# 485.net
KiCad netlist of a schematic drawn in Altium Designer
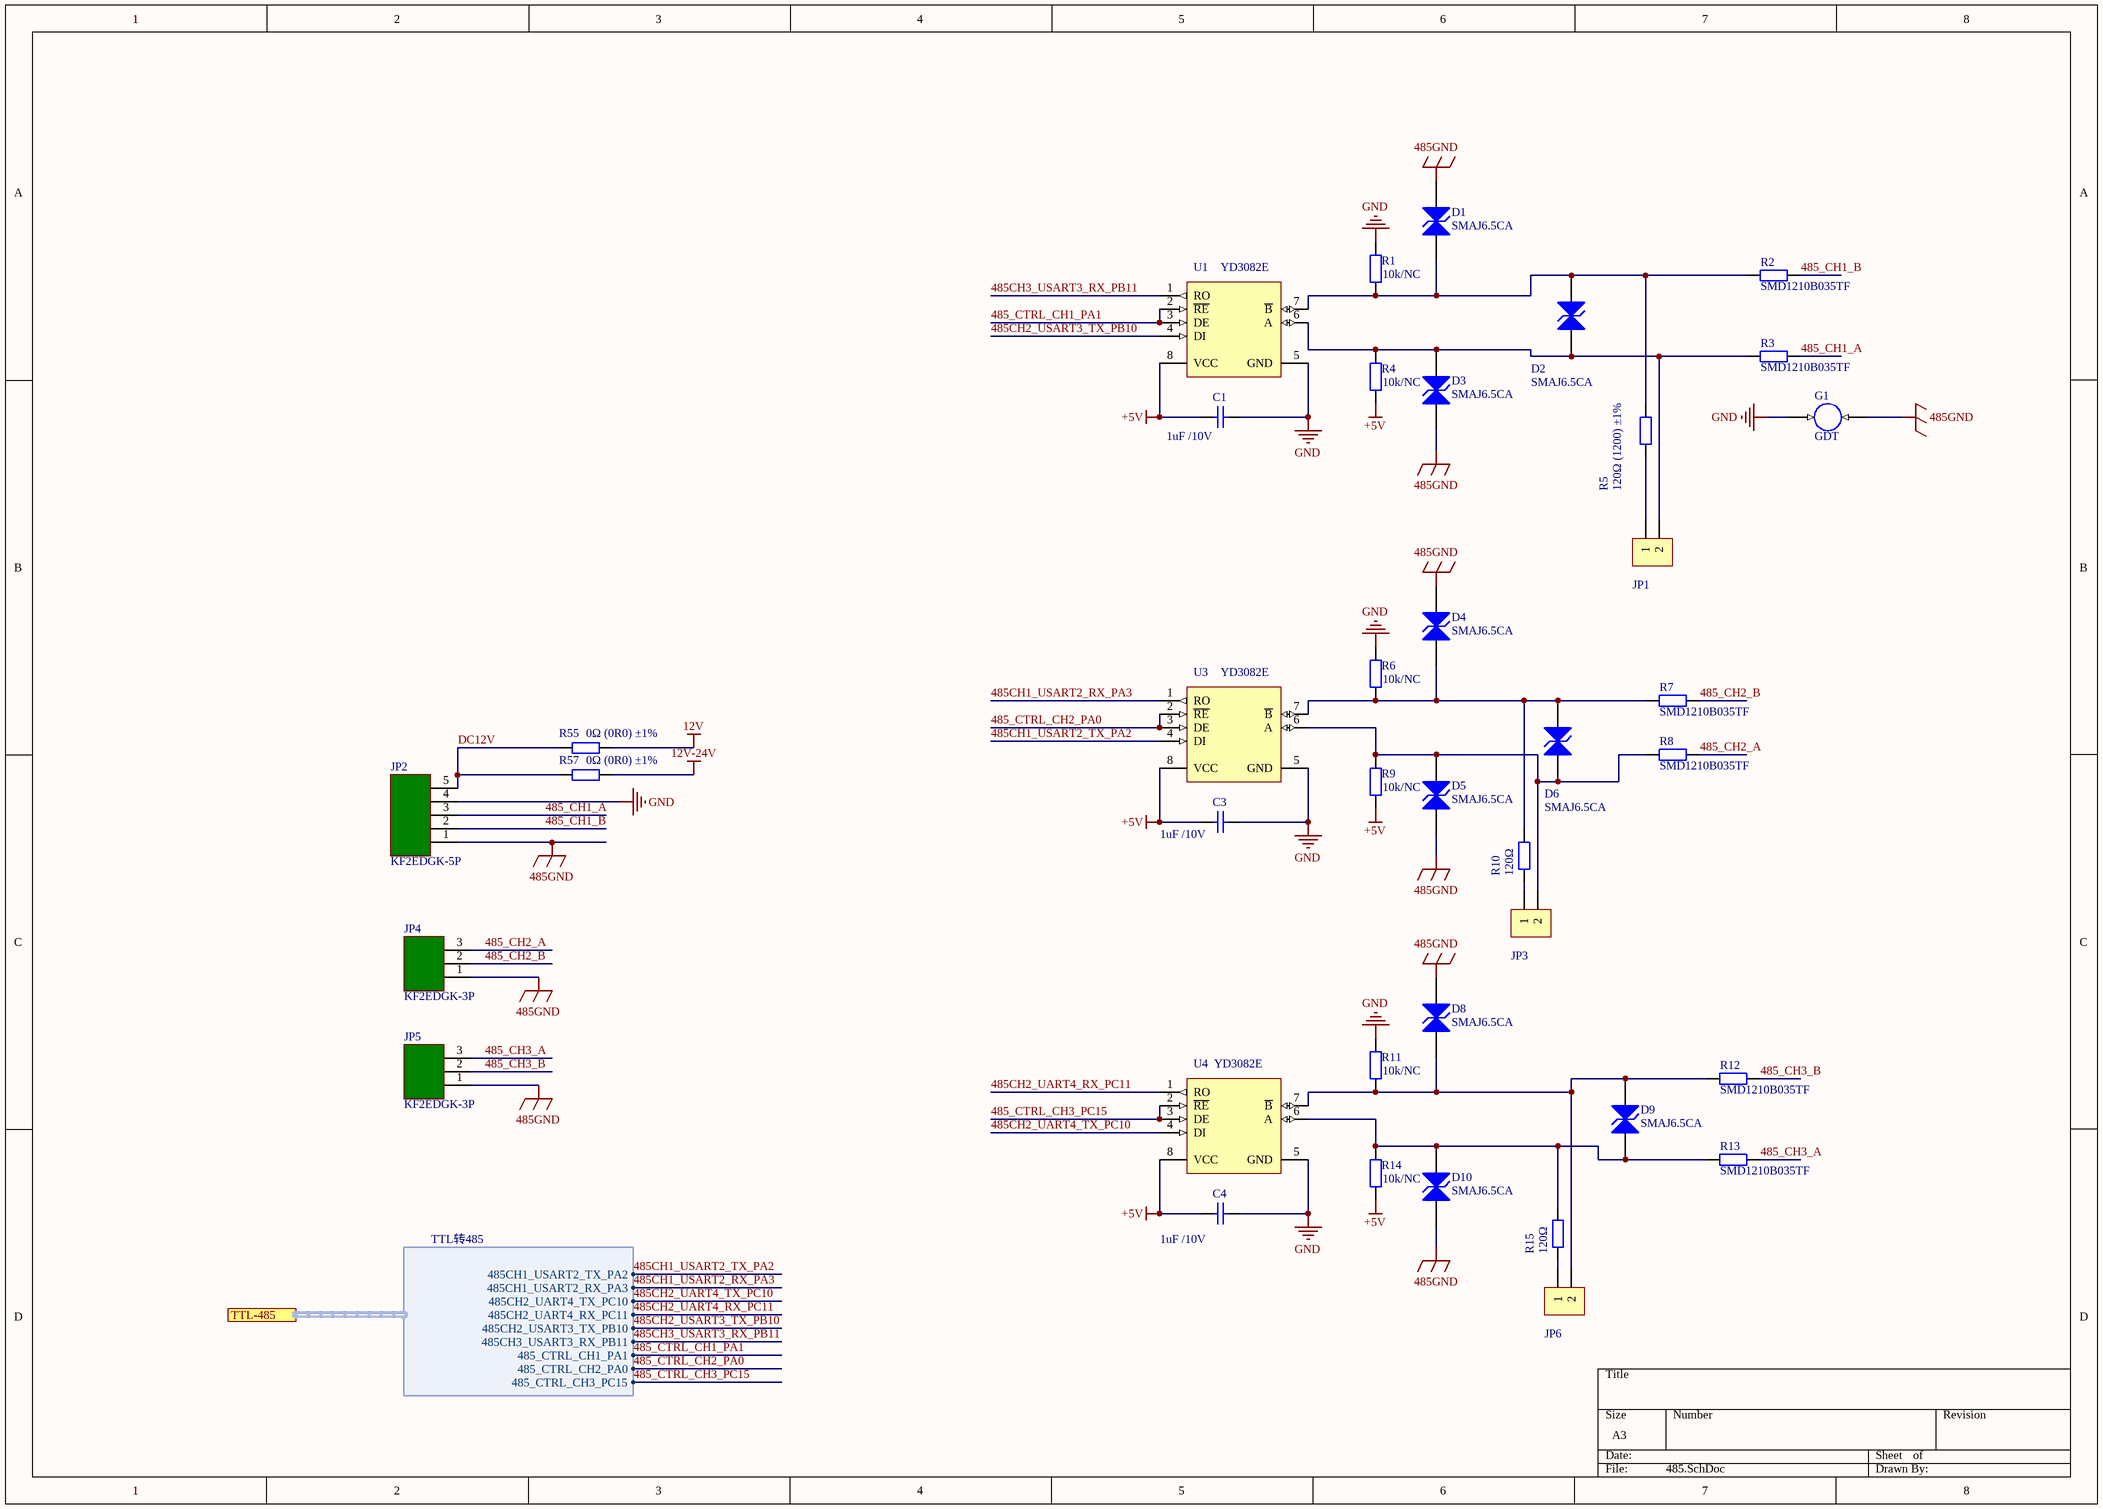
[diagram p0: 485.SchDoc]

(export (version "E")
  (design (tool "Eeschema 10.0.6"))
  (components
    (comp (ref "C1")
      (value "1uF /10V")
      (footprint "0603_C")
      (description "贴片电容")
      (libsource (lib "Miscellaneous Devices LC") (part "0603 100nF (104) 10% 50V"))
    )
    (comp (ref "C3")
      (value "1uF /10V")
      (footprint "0603_C")
      (description "贴片电容")
      (libsource (lib "Miscellaneous Devices LC") (part "0603 100nF (104) 10% 50V"))
    )
    (comp (ref "C4")
      (value "1uF /10V")
      (footprint "0603_C")
      (description "贴片电容")
      (libsource (lib "Miscellaneous Devices LC") (part "0603 100nF (104) 10% 50V"))
    )
    (comp (ref "D1")
      (value "SMAJ6.5CA")
      (footprint "SMA(DO-214AC)_S1")
      (description "TVS")
      (libsource (lib "Miscellaneous Devices LC") (part "SMB/DO-214AA P6SMB6.8CA"))
    )
    (comp (ref "D2")
      (value "SMAJ6.5CA")
      (footprint "SMA(DO-214AC)_S1")
      (description "TVS")
      (libsource (lib "Miscellaneous Devices LC") (part "SMB/DO-214AA P6SMB6.8CA"))
    )
    (comp (ref "D3")
      (value "SMAJ6.5CA")
      (footprint "SMA(DO-214AC)_S1")
      (description "TVS")
      (libsource (lib "Miscellaneous Devices LC") (part "SMB/DO-214AA P6SMB6.8CA"))
    )
    (comp (ref "D4")
      (value "SMAJ6.5CA")
      (footprint "SMA(DO-214AC)_S1")
      (description "TVS")
      (libsource (lib "Miscellaneous Devices LC") (part "SMB/DO-214AA P6SMB6.8CA"))
    )
    (comp (ref "D5")
      (value "SMAJ6.5CA")
      (footprint "SMA(DO-214AC)_S1")
      (description "TVS")
      (libsource (lib "Miscellaneous Devices LC") (part "SMB/DO-214AA P6SMB6.8CA"))
    )
    (comp (ref "D6")
      (value "SMAJ6.5CA")
      (footprint "SMA(DO-214AC)_S1")
      (description "TVS")
      (libsource (lib "Miscellaneous Devices LC") (part "SMB/DO-214AA P6SMB6.8CA"))
    )
    (comp (ref "D8")
      (value "SMAJ6.5CA")
      (footprint "SMA(DO-214AC)_S1")
      (description "TVS")
      (libsource (lib "Miscellaneous Devices LC") (part "SMB/DO-214AA P6SMB6.8CA"))
    )
    (comp (ref "D9")
      (value "SMAJ6.5CA")
      (footprint "SMA(DO-214AC)_S1")
      (description "TVS")
      (libsource (lib "Miscellaneous Devices LC") (part "SMB/DO-214AA P6SMB6.8CA"))
    )
    (comp (ref "D10")
      (value "SMAJ6.5CA")
      (footprint "SMA(DO-214AC)_S1")
      (description "TVS")
      (libsource (lib "Miscellaneous Devices LC") (part "SMB/DO-214AA P6SMB6.8CA"))
    )
    (comp (ref "G1")
      (value "GDT")
      (footprint "GDT")
      (description "放电管")
      (libsource (lib "this") (part "GDT"))
    )
    (comp (ref "JP1")
      (value "HDR-1X2")
      (footprint "HDR-1X2")
      (description "2P接插件")
      (fields (field (name "版权归属") "源创客"))
      (libsource (lib "源创客") (part "Header 2"))
    )
    (comp (ref "JP2")
      (value "KF2EDGK-5P")
      (footprint "KF2EDGK5.08W-5P")
      (libsource (lib "KF2EDGK") (part "KF2EDGK-5P"))
    )
    (comp (ref "JP3")
      (value "HDR-1X2")
      (footprint "HDR-1X2")
      (description "2P接插件")
      (fields (field (name "版权归属") "源创客"))
      (libsource (lib "源创客") (part "Header 2"))
    )
    (comp (ref "JP4")
      (value "KF2EDGK-3P")
      (footprint "KF2EDGK5.08W-3P")
      (libsource (lib "KF2EDGK") (part "KF2EDGK-3P"))
    )
    (comp (ref "JP5")
      (value "KF2EDGK-3P")
      (footprint "KF2EDGK5.08W-3P")
      (libsource (lib "KF2EDGK") (part "KF2EDGK-3P"))
    )
    (comp (ref "JP6")
      (value "HDR-1X2")
      (footprint "HDR-1X2")
      (description "2P接插件")
      (fields (field (name "版权归属") "源创客"))
      (libsource (lib "源创客") (part "Header 2"))
    )
    (comp (ref "R1")
      (value "10k/NC")
      (footprint "0603_R")
      (description "贴片电阻")
      (libsource (lib "Miscellaneous Devices LC") (part "0603 3.3KΩ (3301) 1%"))
    )
    (comp (ref "R2")
      (value "SMD1210B035TF")
      (footprint "1206_R")
      (description "贴片电阻")
      (libsource (lib "Miscellaneous Devices LC") (part "1206 0Ω (0R0) 1%"))
    )
    (comp (ref "R3")
      (value "SMD1210B035TF")
      (footprint "1206_R")
      (description "贴片电阻")
      (libsource (lib "Miscellaneous Devices LC") (part "1206 0Ω (0R0) 1%"))
    )
    (comp (ref "R4")
      (value "10k/NC")
      (footprint "0603_R")
      (description "贴片电阻")
      (libsource (lib "Miscellaneous Devices LC") (part "0603 3.3KΩ (3301) 1%"))
    )
    (comp (ref "R5")
      (value "120Ω (1200) ±1%")
      (footprint "0603_R")
      (description "贴片电阻")
      (libsource (lib "Miscellaneous Devices LC") (part "0603 120Ω (1200) 1%"))
    )
    (comp (ref "R6")
      (value "10k/NC")
      (footprint "0603_R")
      (description "贴片电阻")
      (libsource (lib "Miscellaneous Devices LC") (part "0603 3.3KΩ (3301) 1%"))
    )
    (comp (ref "R7")
      (value "SMD1210B035TF")
      (footprint "1206_R")
      (description "贴片电阻")
      (libsource (lib "Miscellaneous Devices LC") (part "1206 0Ω (0R0) 1%"))
    )
    (comp (ref "R8")
      (value "SMD1210B035TF")
      (footprint "1206_R")
      (description "贴片电阻")
      (libsource (lib "Miscellaneous Devices LC") (part "1206 0Ω (0R0) 1%"))
    )
    (comp (ref "R9")
      (value "10k/NC")
      (footprint "0603_R")
      (description "贴片电阻")
      (libsource (lib "Miscellaneous Devices LC") (part "0603 3.3KΩ (3301) 1%"))
    )
    (comp (ref "R10")
      (value "120Ω")
      (footprint "0603_R")
      (description "贴片电阻")
      (libsource (lib "") (part "0603 120Ω (1200) 1%_1"))
    )
    (comp (ref "R11")
      (value "10k/NC")
      (footprint "0603_R")
      (description "贴片电阻")
      (libsource (lib "Miscellaneous Devices LC") (part "0603 3.3KΩ (3301) 1%"))
    )
    (comp (ref "R12")
      (value "SMD1210B035TF")
      (footprint "1206_R")
      (description "贴片电阻")
      (libsource (lib "Miscellaneous Devices LC") (part "1206 0Ω (0R0) 1%"))
    )
    (comp (ref "R13")
      (value "SMD1210B035TF")
      (footprint "1206_R")
      (description "贴片电阻")
      (libsource (lib "Miscellaneous Devices LC") (part "1206 0Ω (0R0) 1%"))
    )
    (comp (ref "R14")
      (value "10k/NC")
      (footprint "0603_R")
      (description "贴片电阻")
      (libsource (lib "Miscellaneous Devices LC") (part "0603 3.3KΩ (3301) 1%"))
    )
    (comp (ref "R15")
      (value "120Ω")
      (footprint "0603_R")
      (description "贴片电阻")
      (libsource (lib "") (part "0603 120Ω (1200) 1%_1"))
    )
    (comp (ref "R55")
      (value "0Ω (0R0) ±1%")
      (footprint "1206_R")
      (description "贴片电阻")
      (libsource (lib "") (part "1206 0Ω (0R0) 1%_1"))
    )
    (comp (ref "R57")
      (value "0Ω (0R0) ±1%")
      (footprint "1206_R")
      (description "贴片电阻")
      (libsource (lib "") (part "1206 0Ω (0R0) 1%_1"))
    )
    (comp (ref "U1")
      (value "YD3082E")
      (footprint "SOIC-8_150mil")
      (description "RS-485/RS-422")
      (libsource (lib "Miscellaneous Devices LC") (part "SP485EEN-L/TR"))
    )
    (comp (ref "U3")
      (value "YD3082E")
      (footprint "SOIC-8_150mil")
      (description "RS-485/RS-422")
      (libsource (lib "Miscellaneous Devices LC") (part "SP485EEN-L/TR"))
    )
    (comp (ref "U4")
      (value "YD3082E")
      (footprint "SOIC-8_150mil")
      (description "RS-485/RS-422")
      (libsource (lib "Miscellaneous Devices LC") (part "SP485EEN-L/TR"))
    )
  )
  (nets
    (net (code "2") (name "+5V") (class "Default")
      (node (ref "C1") (pin "1") (pinfunction "1_1") (pintype "passive"))
      (node (ref "C3") (pin "1") (pinfunction "1_1") (pintype "passive"))
      (node (ref "C4") (pin "1") (pinfunction "1_1") (pintype "passive"))
      (node (ref "R14") (pin "1") (pinfunction "1_1") (pintype "passive"))
      (node (ref "R4") (pin "1") (pinfunction "1_1") (pintype "passive"))
      (node (ref "R9") (pin "1") (pinfunction "1_1") (pintype "passive"))
      (node (ref "U1") (pin "8") (pinfunction "VCC_8") (pintype "power_in"))
      (node (ref "U3") (pin "8") (pinfunction "VCC_8") (pintype "power_in"))
      (node (ref "U4") (pin "8") (pinfunction "VCC_8") (pintype "power_in"))
    )
    (net (code "3") (name "/485CH1_USART2_RX_PA3") (class "Default")
      (node (ref "U3") (pin "1") (pinfunction "RO_1") (pintype "output"))
    )
    (net (code "4") (name "/485CH1_USART2_TX_PA2") (class "Default")
      (node (ref "U3") (pin "4") (pinfunction "DI_4") (pintype "input"))
    )
    (net (code "5") (name "/485CH2_UART4_RX_PC11") (class "Default")
      (node (ref "U4") (pin "1") (pinfunction "RO_1") (pintype "output"))
    )
    (net (code "6") (name "/485CH2_UART4_TX_PC10") (class "Default")
      (node (ref "U4") (pin "4") (pinfunction "DI_4") (pintype "input"))
    )
    (net (code "7") (name "/485CH2_USART3_TX_PB10") (class "Default")
      (node (ref "U1") (pin "4") (pinfunction "DI_4") (pintype "input"))
    )
    (net (code "8") (name "/485CH3_USART3_RX_PB11") (class "Default")
      (node (ref "U1") (pin "1") (pinfunction "RO_1") (pintype "output"))
    )
    (net (code "9") (name "/485_CH1_A") (class "Default")
      (node (ref "JP2") (pin "3") (pinfunction "3_3") (pintype "passive"))
      (node (ref "R3") (pin "2") (pinfunction "2_2") (pintype "passive"))
    )
    (net (code "10") (name "/485_CH1_B") (class "Default")
      (node (ref "JP2") (pin "2") (pinfunction "2_2") (pintype "passive"))
      (node (ref "R2") (pin "2") (pinfunction "2_2") (pintype "passive"))
    )
    (net (code "11") (name "/485_CH2_A") (class "Default")
      (node (ref "JP4") (pin "3") (pinfunction "3_3") (pintype "passive"))
      (node (ref "R8") (pin "2") (pinfunction "2_2") (pintype "passive"))
    )
    (net (code "12") (name "/485_CH2_B") (class "Default")
      (node (ref "JP4") (pin "2") (pinfunction "2_2") (pintype "passive"))
      (node (ref "R7") (pin "2") (pinfunction "2_2") (pintype "passive"))
    )
    (net (code "13") (name "/485_CH3_A") (class "Default")
      (node (ref "JP5") (pin "3") (pinfunction "3_3") (pintype "passive"))
      (node (ref "R13") (pin "2") (pinfunction "2_2") (pintype "passive"))
    )
    (net (code "14") (name "/485_CH3_B") (class "Default")
      (node (ref "JP5") (pin "2") (pinfunction "2_2") (pintype "passive"))
      (node (ref "R12") (pin "2") (pinfunction "2_2") (pintype "passive"))
    )
    (net (code "15") (name "/485_CTRL_CH1_PA1") (class "Default")
      (node (ref "U1") (pin "2") (pinfunction "~{RE}_2") (pintype "input"))
      (node (ref "U1") (pin "3") (pinfunction "DE_3") (pintype "input"))
    )
    (net (code "16") (name "/485_CTRL_CH2_PA0") (class "Default")
      (node (ref "U3") (pin "2") (pinfunction "~{RE}_2") (pintype "input"))
      (node (ref "U3") (pin "3") (pinfunction "DE_3") (pintype "input"))
    )
    (net (code "17") (name "/485_CTRL_CH3_PC15") (class "Default")
      (node (ref "U4") (pin "2") (pinfunction "~{RE}_2") (pintype "input"))
      (node (ref "U4") (pin "3") (pinfunction "DE_3") (pintype "input"))
    )
    (net (code "18") (name "/DC12V") (class "Default")
      (node (ref "JP2") (pin "5") (pinfunction "5_5") (pintype "passive"))
      (node (ref "R55") (pin "2") (pinfunction "2_2") (pintype "passive"))
      (node (ref "R57") (pin "2") (pinfunction "2_2") (pintype "passive"))
    )
    (net (code "20") (name "12V") (class "Default")
      (node (ref "R55") (pin "1") (pinfunction "1_1") (pintype "passive"))
    )
    (net (code "21") (name "12V-24V") (class "Default")
      (node (ref "R57") (pin "1") (pinfunction "1_1") (pintype "passive"))
    )
    (net (code "22") (name "485GND") (class "Default")
      (node (ref "D1") (pin "1") (pinfunction "A_1") (pintype "passive"))
      (node (ref "D10") (pin "1") (pinfunction "A_1") (pintype "passive"))
      (node (ref "D3") (pin "1") (pinfunction "A_1") (pintype "passive"))
      (node (ref "D4") (pin "1") (pinfunction "A_1") (pintype "passive"))
      (node (ref "D5") (pin "1") (pinfunction "A_1") (pintype "passive"))
      (node (ref "D8") (pin "1") (pinfunction "A_1") (pintype "passive"))
      (node (ref "G1") (pin "1") (pinfunction "1_1") (pintype "input"))
      (node (ref "JP2") (pin "1") (pinfunction "1_1") (pintype "passive"))
      (node (ref "JP4") (pin "1") (pinfunction "1_1") (pintype "passive"))
      (node (ref "JP5") (pin "1") (pinfunction "1_1") (pintype "passive"))
    )
    (net (code "23") (name "GND") (class "Default")
      (node (ref "C1") (pin "2") (pinfunction "2_2") (pintype "passive"))
      (node (ref "C3") (pin "2") (pinfunction "2_2") (pintype "passive"))
      (node (ref "C4") (pin "2") (pinfunction "2_2") (pintype "passive"))
      (node (ref "G1") (pin "2") (pinfunction "2_2") (pintype "input"))
      (node (ref "JP2") (pin "4") (pinfunction "4_4") (pintype "passive"))
      (node (ref "R1") (pin "2") (pinfunction "2_2") (pintype "passive"))
      (node (ref "R11") (pin "2") (pinfunction "2_2") (pintype "passive"))
      (node (ref "R6") (pin "2") (pinfunction "2_2") (pintype "passive"))
      (node (ref "U1") (pin "5") (pinfunction "GND_5") (pintype "power_in"))
      (node (ref "U3") (pin "5") (pinfunction "GND_5") (pintype "power_in"))
      (node (ref "U4") (pin "5") (pinfunction "GND_5") (pintype "power_in"))
    )
    (net (code "24") (name "Net-(D1-K)") (class "Default")
      (node (ref "D1") (pin "2") (pinfunction "K_2") (pintype "passive"))
      (node (ref "D2") (pin "1") (pinfunction "A_1") (pintype "passive"))
      (node (ref "R1") (pin "1") (pinfunction "1_1") (pintype "passive"))
      (node (ref "R2") (pin "1") (pinfunction "1_1") (pintype "passive"))
      (node (ref "R5") (pin "1") (pinfunction "1_1") (pintype "passive"))
      (node (ref "U1") (pin "7") (pinfunction "~{B}_7") (pintype "bidirectional"))
    )
    (net (code "25") (name "Net-(D2-K)") (class "Default")
      (node (ref "D2") (pin "2") (pinfunction "K_2") (pintype "passive"))
      (node (ref "D3") (pin "2") (pinfunction "K_2") (pintype "passive"))
      (node (ref "JP1") (pin "2") (pinfunction "2_2") (pintype "passive"))
      (node (ref "R3") (pin "1") (pinfunction "1_1") (pintype "passive"))
      (node (ref "R4") (pin "2") (pinfunction "2_2") (pintype "passive"))
      (node (ref "U1") (pin "6") (pinfunction "A_6") (pintype "bidirectional"))
    )
    (net (code "26") (name "Net-(D4-K)") (class "Default")
      (node (ref "D4") (pin "2") (pinfunction "K_2") (pintype "passive"))
      (node (ref "D6") (pin "1") (pinfunction "A_1") (pintype "passive"))
      (node (ref "R10") (pin "2") (pinfunction "2_2") (pintype "passive"))
      (node (ref "R6") (pin "1") (pinfunction "1_1") (pintype "passive"))
      (node (ref "R7") (pin "1") (pinfunction "1_1") (pintype "passive"))
      (node (ref "U3") (pin "7") (pinfunction "~{B}_7") (pintype "bidirectional"))
    )
    (net (code "27") (name "Net-(D5-K)") (class "Default")
      (node (ref "D5") (pin "2") (pinfunction "K_2") (pintype "passive"))
      (node (ref "D6") (pin "2") (pinfunction "K_2") (pintype "passive"))
      (node (ref "JP3") (pin "2") (pinfunction "2_2") (pintype "passive"))
      (node (ref "R8") (pin "1") (pinfunction "1_1") (pintype "passive"))
      (node (ref "R9") (pin "2") (pinfunction "2_2") (pintype "passive"))
      (node (ref "U3") (pin "6") (pinfunction "A_6") (pintype "bidirectional"))
    )
    (net (code "28") (name "Net-(D8-K)") (class "Default")
      (node (ref "D8") (pin "2") (pinfunction "K_2") (pintype "passive"))
      (node (ref "D9") (pin "1") (pinfunction "A_1") (pintype "passive"))
      (node (ref "JP6") (pin "2") (pinfunction "2_2") (pintype "passive"))
      (node (ref "R11") (pin "1") (pinfunction "1_1") (pintype "passive"))
      (node (ref "R12") (pin "1") (pinfunction "1_1") (pintype "passive"))
      (node (ref "U4") (pin "7") (pinfunction "~{B}_7") (pintype "bidirectional"))
    )
    (net (code "29") (name "Net-(D10-K)") (class "Default")
      (node (ref "D10") (pin "2") (pinfunction "K_2") (pintype "passive"))
      (node (ref "D9") (pin "2") (pinfunction "K_2") (pintype "passive"))
      (node (ref "R13") (pin "1") (pinfunction "1_1") (pintype "passive"))
      (node (ref "R14") (pin "2") (pinfunction "2_2") (pintype "passive"))
      (node (ref "R15") (pin "2") (pinfunction "2_2") (pintype "passive"))
      (node (ref "U4") (pin "6") (pinfunction "A_6") (pintype "bidirectional"))
    )
    (net (code "30") (name "Net-(JP1-Pad1)") (class "Default")
      (node (ref "JP1") (pin "1") (pinfunction "1_1") (pintype "passive"))
      (node (ref "R5") (pin "2") (pinfunction "2_2") (pintype "passive"))
    )
    (net (code "31") (name "Net-(JP3-Pad1)") (class "Default")
      (node (ref "JP3") (pin "1") (pinfunction "1_1") (pintype "passive"))
      (node (ref "R10") (pin "1") (pinfunction "1_1") (pintype "passive"))
    )
    (net (code "32") (name "Net-(JP6-Pad1)") (class "Default")
      (node (ref "JP6") (pin "1") (pinfunction "1_1") (pintype "passive"))
      (node (ref "R15") (pin "1") (pinfunction "1_1") (pintype "passive"))
    )
  )
)
